# smart_stirrer_proto_mk2.net
KiCad netlist of a schematic drawn in EAGLE
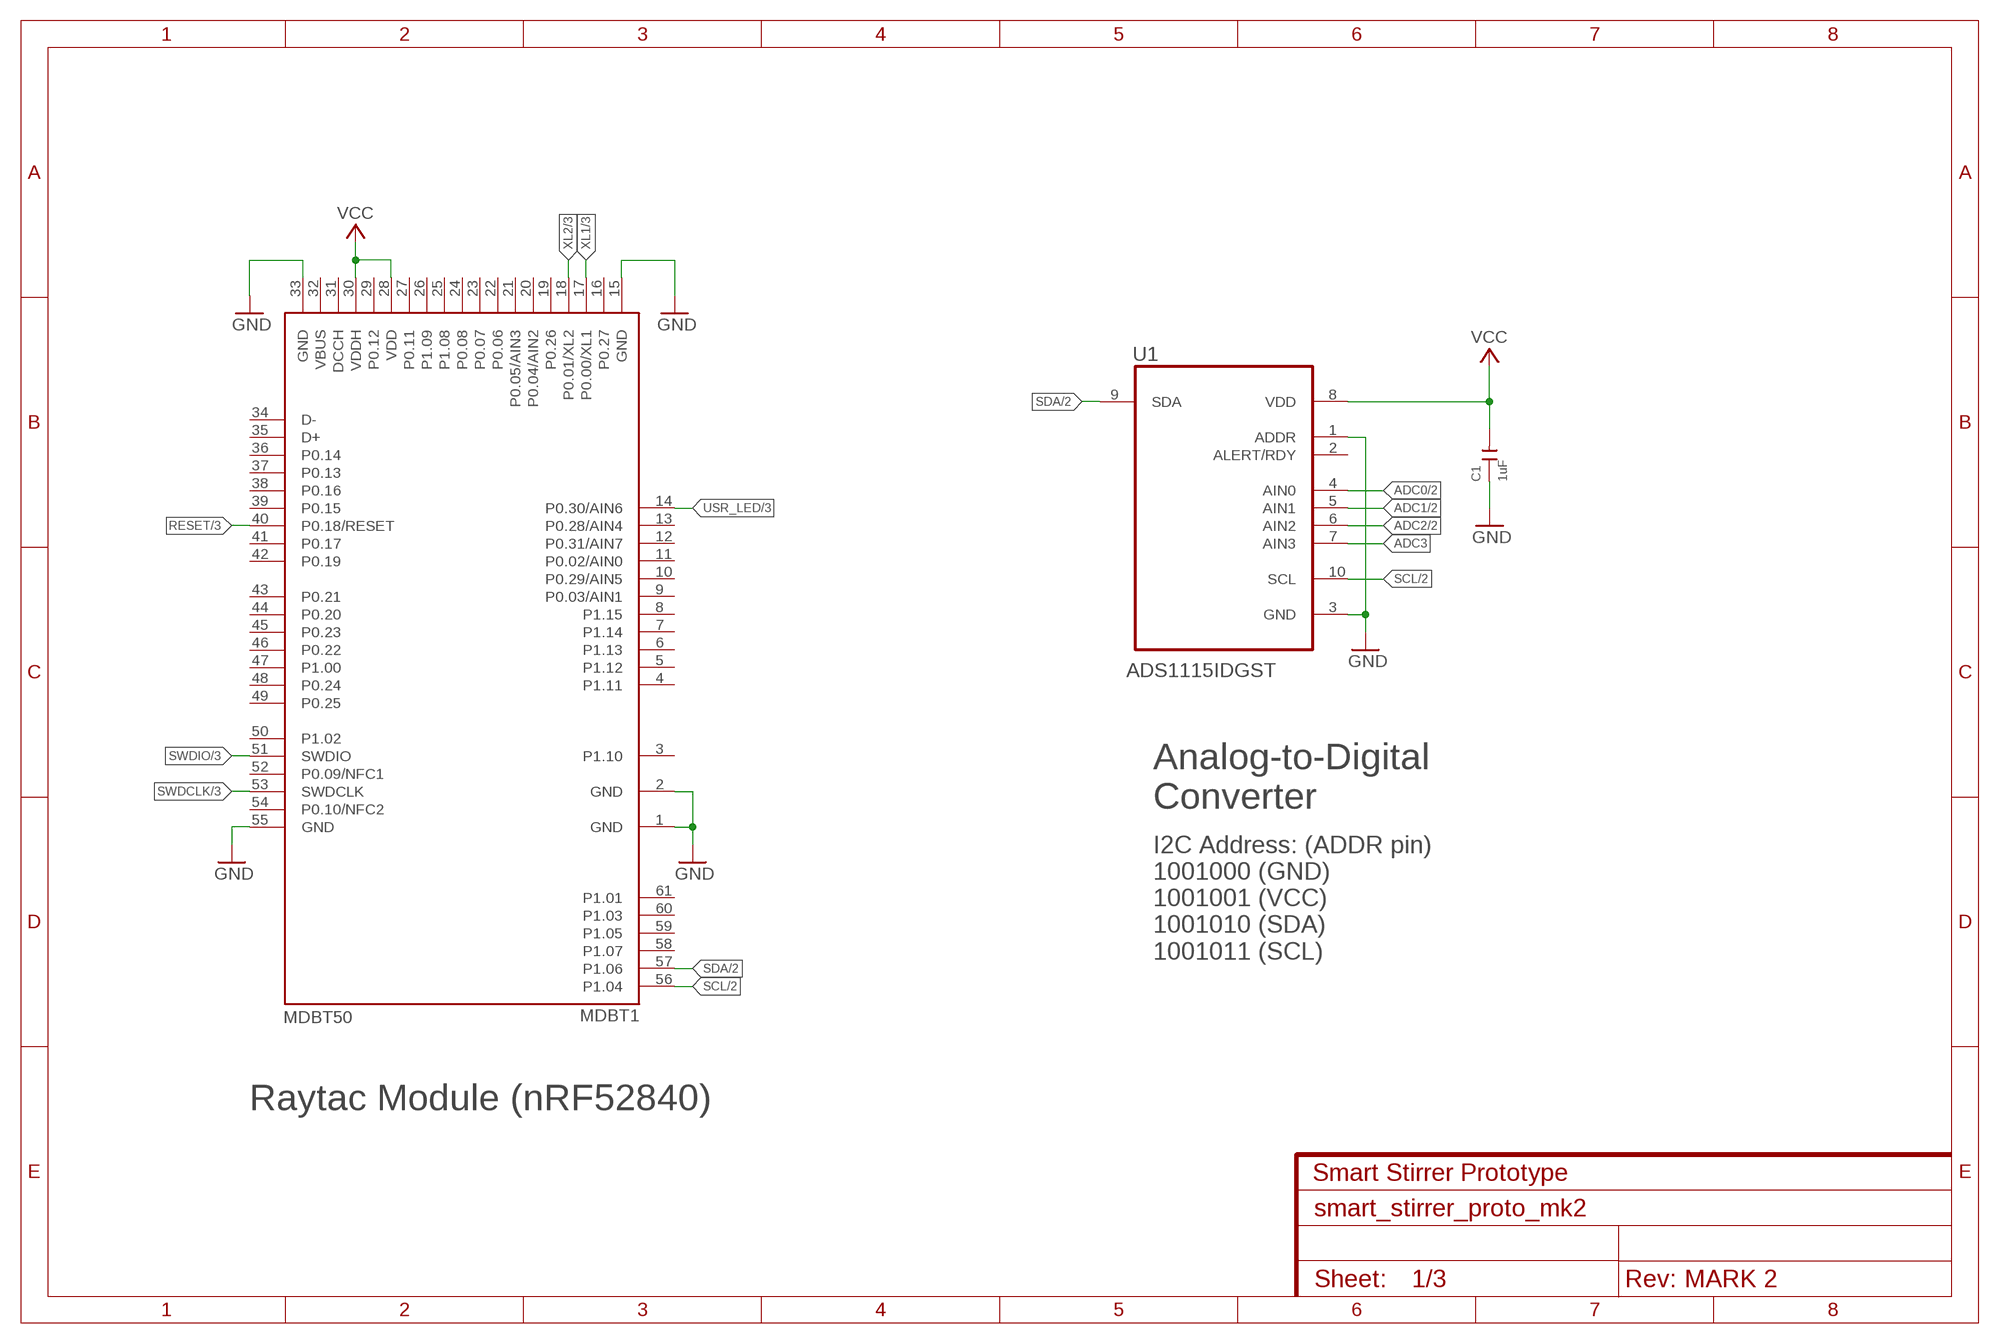
[diagram p0: schematic, sheet 1]
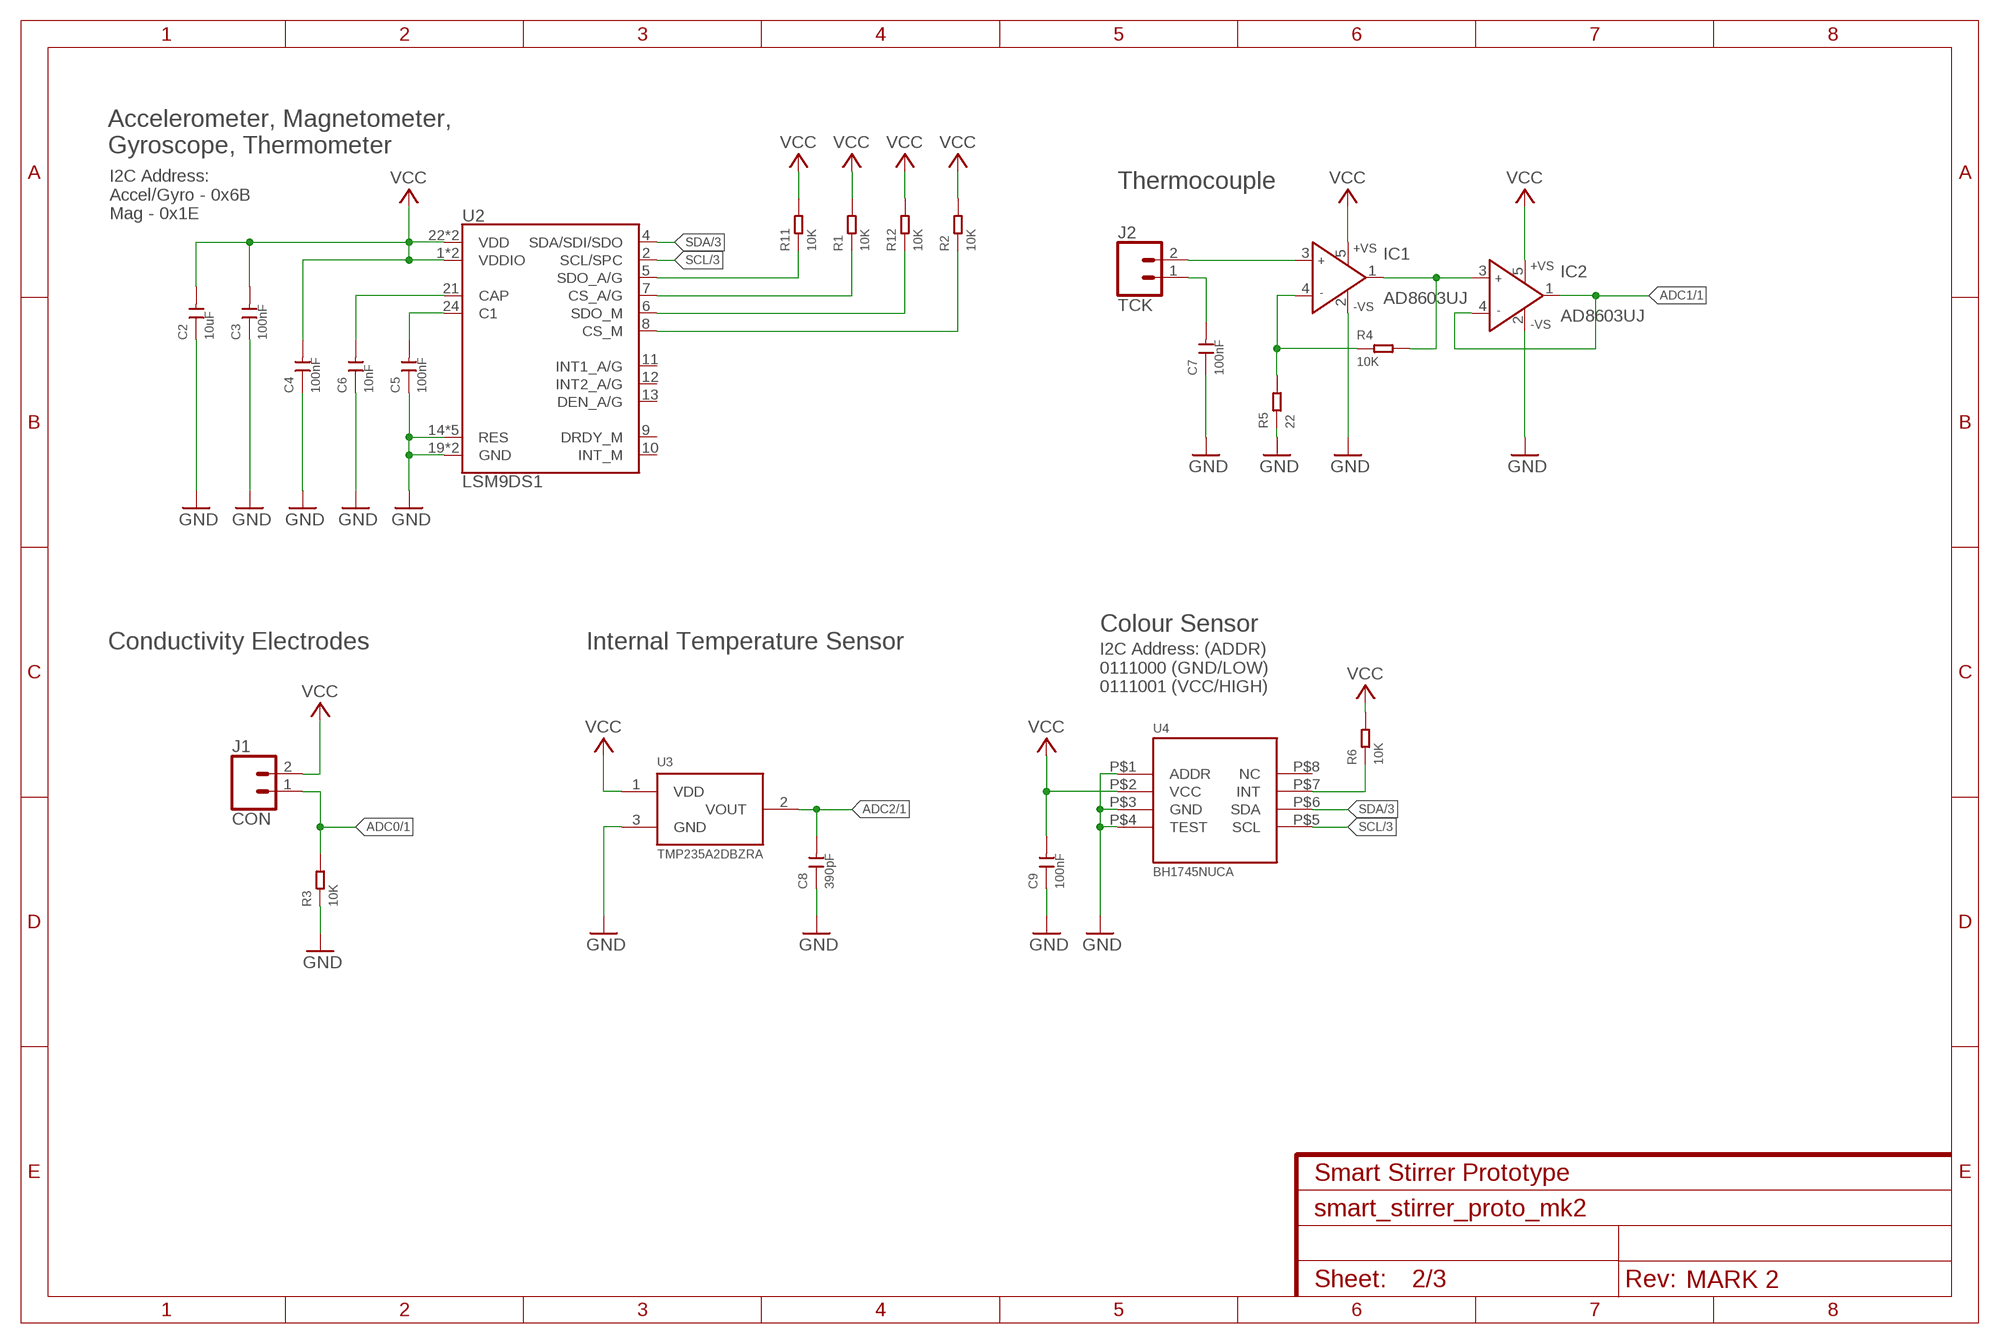
[diagram p1: schematic, sheet 2]
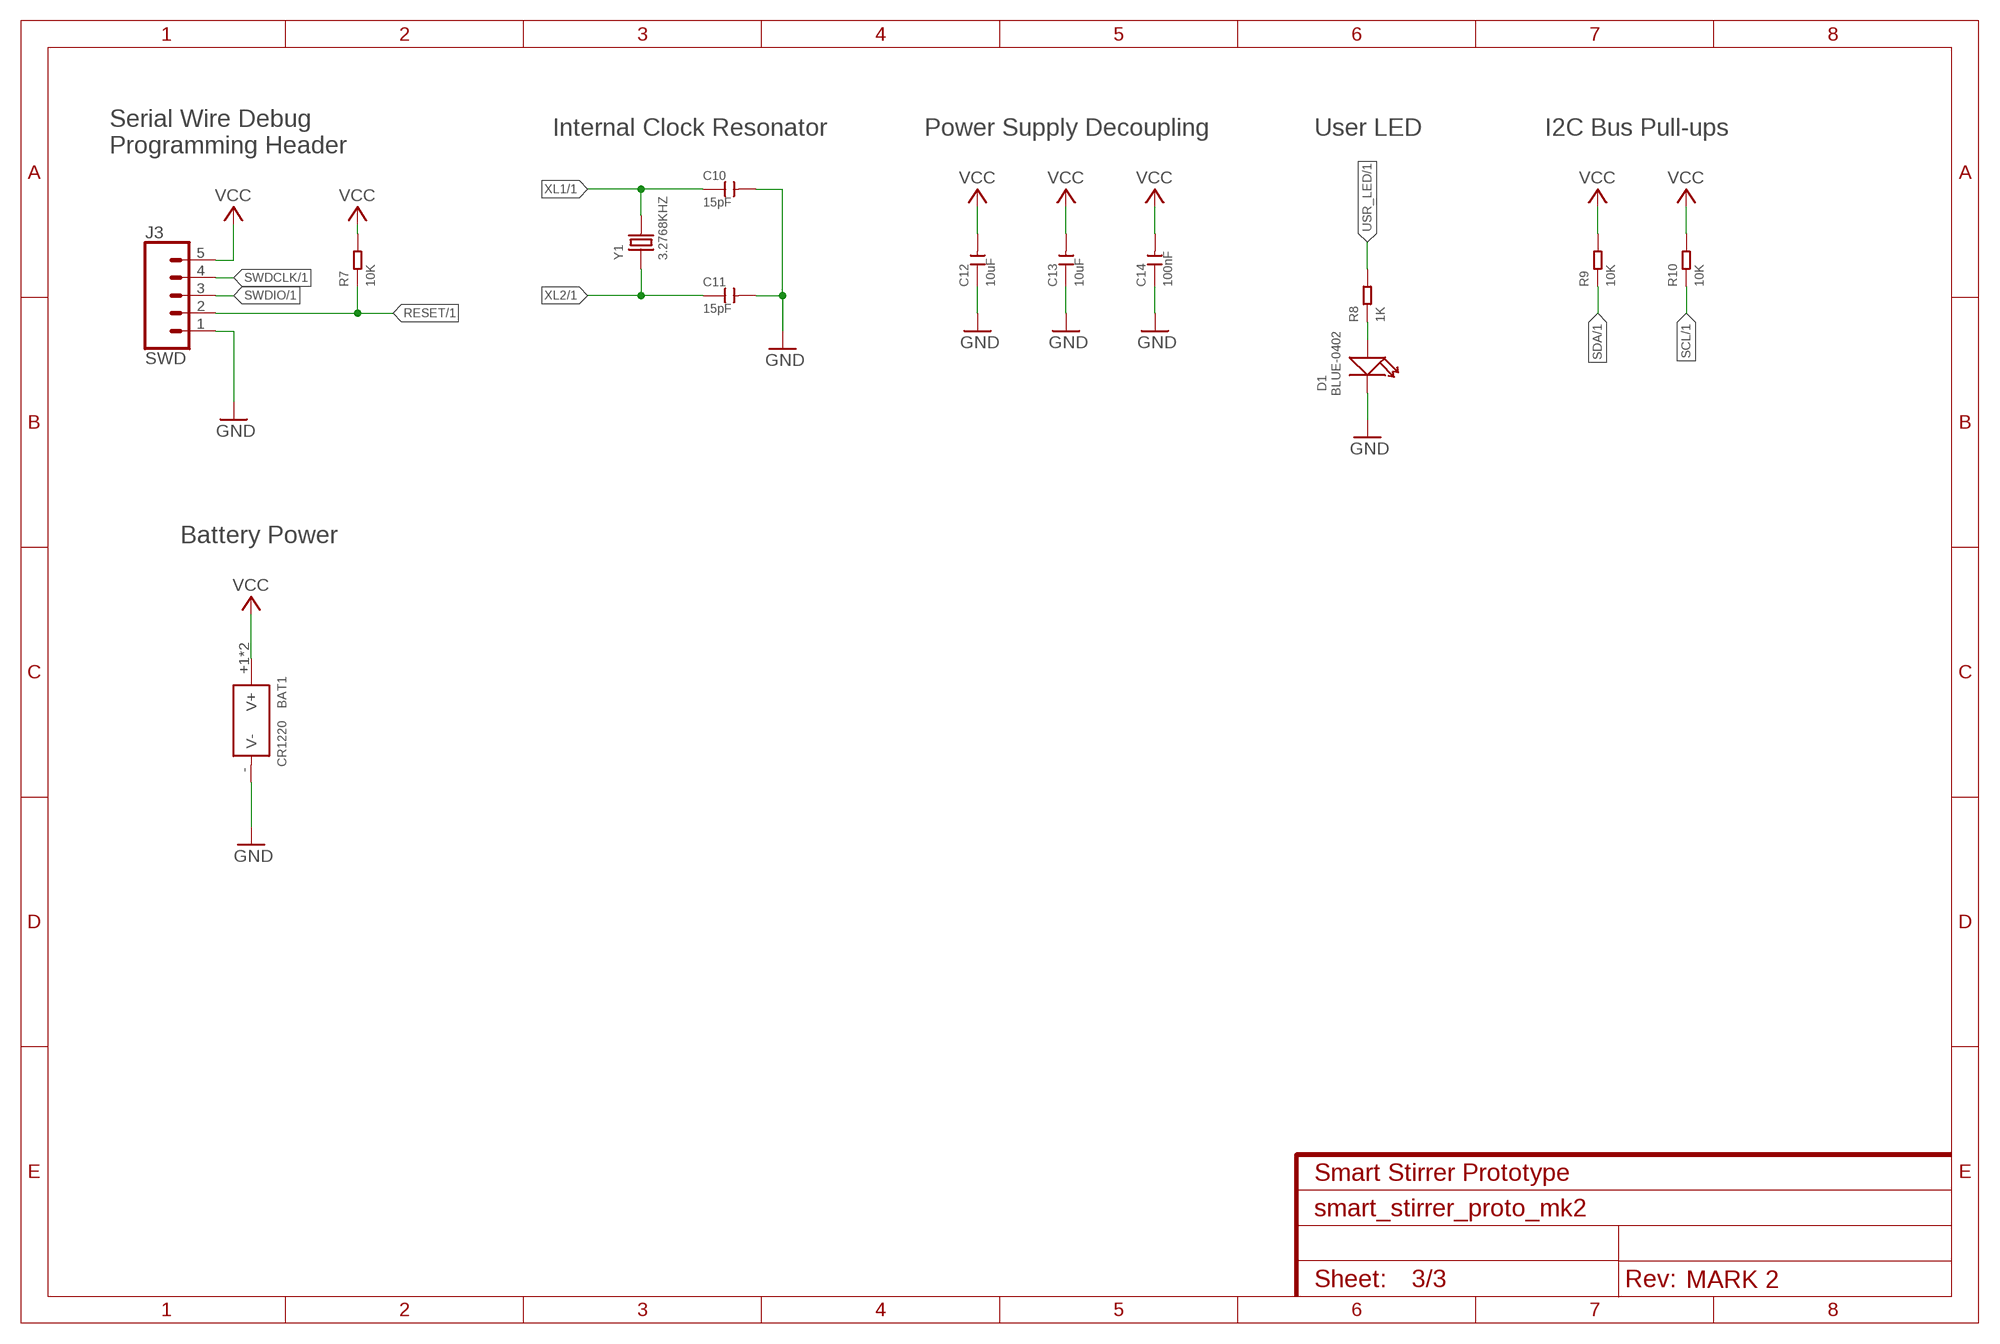
[diagram p2: schematic, sheet 3]

(export (version "E")
  (design (tool "Eeschema 10.0.6"))
  (components
    (comp (ref "C2")
      (value "10uF")
      (footprint "eagle-import:C0402")
      (fields (field (name "MPN") "CC0402MRX5R5BB106"))
      (libsource (lib "eagle-import") (part "CERAMIC-10UF-6.3V-20%-X5R(0402)"))
    )
    (comp (ref "C3")
      (value "100nF")
      (footprint "eagle-import:C0402")
      (fields (field (name "MPN") "CC0402KRX7R8BB104"))
      (libsource (lib "eagle-import") (part "CERAMIC-100NF-25V-10%-X7R(0402)"))
    )
    (comp (ref "C4")
      (value "100nF")
      (footprint "eagle-import:C0402")
      (fields (field (name "MPN") "CC0402KRX7R8BB104"))
      (libsource (lib "eagle-import") (part "CERAMIC-100NF-25V-10%-X7R(0402)"))
    )
    (comp (ref "C5")
      (value "100nF")
      (footprint "eagle-import:C0402")
      (fields (field (name "MPN") "CC0402KRX7R8BB104"))
      (libsource (lib "eagle-import") (part "CERAMIC-100NF-25V-10%-X7R(0402)"))
    )
    (comp (ref "C6")
      (value "10nF")
      (footprint "eagle-import:C0402")
      (fields (field (name "MPN") "CC0402KRX7R9BB103"))
      (libsource (lib "eagle-import") (part "CERAMIC-10NF-50V-10%-X7R(0402)"))
    )
    (comp (ref "C7")
      (value "100nF")
      (footprint "eagle-import:C0402")
      (fields (field (name "MPN") "CC0402KRX7R8BB104"))
      (libsource (lib "eagle-import") (part "OPL_Capacitor_8004261_CERAMIC-100NF-25V-10%-X7R(0402)"))
    )
    (comp (ref "C8")
      (value "390pF")
      (footprint "eagle-import:C0402")
      (fields (field (name "MPN") "CC0402KRX7R9BB391"))
      (libsource (lib "eagle-import") (part "CERAMIC-390PF-50V-10%-X7R(0402)"))
    )
    (comp (ref "C9")
      (value "100nF")
      (footprint "eagle-import:C0402")
      (fields (field (name "MPN") "CC0402KRX7R8BB104"))
      (libsource (lib "eagle-import") (part "OPL_Capacitor_8004261_CERAMIC-100NF-25V-10%-X7R(0402)"))
    )
    (comp (ref "IC1")
      (value "AD8603UJ")
      (footprint "eagle-import:SOT23-5")
      (fields (field (name "MF") "ALTERA CORPORATION") (field (name "MPN") "AD8603AUJZ-REEL7"))
      (libsource (lib "eagle-import") (part "AD8603UJ"))
    )
    (comp (ref "IC2")
      (value "AD8603UJ")
      (footprint "eagle-import:SOT23-5")
      (fields (field (name "MF") "ALTERA CORPORATION") (field (name "MPN") "AD8603AUJZ-REEL7"))
      (libsource (lib "eagle-import") (part "AD8603UJ"))
    )
    (comp (ref "J1")
      (value "CON")
      (footprint "eagle-import:1X02_NO_SILK")
      (libsource (lib "eagle-import") (part "CONN_021X02_NO_SILK"))
    )
    (comp (ref "J2")
      (value "TCK")
      (footprint "eagle-import:1X02_NO_SILK")
      (libsource (lib "eagle-import") (part "CONN_021X02_NO_SILK"))
    )
    (comp (ref "R1")
      (value "10K")
      (footprint "eagle-import:R0402")
      (fields (field (name "MPN") "RC0402JR-0710KL"))
      (libsource (lib "eagle-import") (part "SMD-RES-10K-5%-1/(0402)"))
    )
    (comp (ref "R2")
      (value "10K")
      (footprint "eagle-import:R0402")
      (fields (field (name "MPN") "RC0402JR-0710KL"))
      (libsource (lib "eagle-import") (part "SMD-RES-10K-5%-1/(0402)"))
    )
    (comp (ref "R3")
      (value "10K")
      (footprint "eagle-import:R0402")
      (fields (field (name "MPN") "RC0402JR-0710KL"))
      (libsource (lib "eagle-import") (part "SMD-RES-10K-5%-1/(0402)"))
    )
    (comp (ref "R4")
      (value "10K")
      (footprint "eagle-import:R0402")
      (fields (field (name "MPN") "RC0402JR-0710KL"))
      (libsource (lib "eagle-import") (part "SMD-RES-10K-5%-1/(0402)"))
    )
    (comp (ref "R5")
      (value "22")
      (footprint "eagle-import:R0402")
      (fields (field (name "MPN") "RC0402JR-070RL"))
      (libsource (lib "eagle-import") (part "SMD-RES-22R-5%-1/16W(0402)"))
    )
    (comp (ref "R6")
      (value "10K")
      (footprint "eagle-import:R0402")
      (fields (field (name "MPN") "RC0402JR-0710KL"))
      (libsource (lib "eagle-import") (part "SMD-RES-10K-5%-1/(0402)"))
    )
    (comp (ref "R11")
      (value "10K")
      (footprint "eagle-import:R0402")
      (fields (field (name "MPN") "RC0402JR-0710KL"))
      (libsource (lib "eagle-import") (part "SMD-RES-10K-5%-1/(0402)"))
    )
    (comp (ref "R12")
      (value "10K")
      (footprint "eagle-import:R0402")
      (fields (field (name "MPN") "RC0402JR-0710KL"))
      (libsource (lib "eagle-import") (part "SMD-RES-10K-5%-1/(0402)"))
    )
    (comp (ref "U2")
      (value "LSM9DS1")
      (footprint "eagle-import:LGA24-8X4")
      (libsource (lib "eagle-import") (part "LSM9DS1"))
    )
    (comp (ref "U3")
      (value "TMP235A2DBZRA")
      (footprint "eagle-import:SOT-23-3")
      (libsource (lib "eagle-import") (part "TMP235A2DBZRA"))
    )
    (comp (ref "U4")
      (value "BH1745NUCA")
      (footprint "eagle-import:BH1745NUC-E2")
      (libsource (lib "eagle-import") (part "BH1745NUCA"))
    )
    (comp (ref "C1")
      (value "1uF")
      (footprint "eagle-import:C0402")
      (fields (field (name "MPN") "CC0402KRX5R6BB105"))
      (libsource (lib "eagle-import") (part "CERAMIC-1UF-10V-10%-X5R(0402)"))
    )
    (comp (ref "MDBT1")
      (value "MDBT50")
      (footprint "eagle-import:MDBT50")
      (libsource (lib "eagle-import") (part "MDBT50"))
    )
    (comp (ref "U1")
      (value "ADS1115IDGST")
      (footprint "eagle-import:SOP50P490X110-10N")
      (fields (field (name "MF") "Texas Instruments"))
      (libsource (lib "eagle-import") (part "ADS1115IDGST"))
    )
    (comp (ref "BAT1")
      (value "CR1220")
      (footprint "eagle-import:BAT2P-13.5-CR1220")
      (libsource (lib "eagle-import") (part "DIP-BATTERY-CELL-HOLDER(1220)"))
    )
    (comp (ref "C10")
      (value "15pF")
      (footprint "eagle-import:C0402")
      (fields (field (name "MPN") "GRM1555C1H150JA01D"))
      (libsource (lib "eagle-import") (part "CERAMIC-15PF-50V-5%-NPO(0402)"))
    )
    (comp (ref "C11")
      (value "15pF")
      (footprint "eagle-import:C0402")
      (fields (field (name "MPN") "GRM1555C1H150JA01D"))
      (libsource (lib "eagle-import") (part "CERAMIC-15PF-50V-5%-NPO(0402)"))
    )
    (comp (ref "C12")
      (value "10uF")
      (footprint "eagle-import:C0402")
      (fields (field (name "MPN") "CC0402MRX5R5BB106"))
      (libsource (lib "eagle-import") (part "OPL_Capacitor_8004261_CERAMIC-10UF-6.3V-20%-X5R(0402)"))
    )
    (comp (ref "C13")
      (value "10uF")
      (footprint "eagle-import:C0402")
      (fields (field (name "MPN") "CC0402MRX5R5BB106"))
      (libsource (lib "eagle-import") (part "OPL_Capacitor_8004261_CERAMIC-10UF-6.3V-20%-X5R(0402)"))
    )
    (comp (ref "C14")
      (value "100nF")
      (footprint "eagle-import:C0402")
      (fields (field (name "MPN") "CC0402KRX7R8BB104"))
      (libsource (lib "eagle-import") (part "OPL_Capacitor_8004261_CERAMIC-100NF-25V-10%-X7R(0402)"))
    )
    (comp (ref "D1")
      (value "BLUE-0402")
      (footprint "eagle-import:LED-0402")
      (fields (field (name "MPN") "BL-HB337A-AV-TRB"))
      (libsource (lib "eagle-import") (part "SMD-LED-CLEAR-BLUE(0402)"))
    )
    (comp (ref "J3")
      (value "SWD")
      (footprint "eagle-import:1X05_NO_SILK")
      (libsource (lib "eagle-import") (part "CONN_05NO_SILK"))
    )
    (comp (ref "R7")
      (value "10K")
      (footprint "eagle-import:R0402")
      (fields (field (name "MPN") "RC0402JR-0710KL"))
      (libsource (lib "eagle-import") (part "SMD-RES-10K-5%-1/(0402)"))
    )
    (comp (ref "R8")
      (value "1K")
      (footprint "eagle-import:R0402")
      (fields (field (name "MPN") "RC0402JR-071KL"))
      (libsource (lib "eagle-import") (part "SMD-RES-1K-5%-1/16W(0402)"))
    )
    (comp (ref "R9")
      (value "10K")
      (footprint "eagle-import:R0402")
      (fields (field (name "MPN") "RC0402JR-0710KL"))
      (libsource (lib "eagle-import") (part "SMD-RES-10K-5%-1/(0402)"))
    )
    (comp (ref "R10")
      (value "10K")
      (footprint "eagle-import:R0402")
      (fields (field (name "MPN") "RC0402JR-0710KL"))
      (libsource (lib "eagle-import") (part "SMD-RES-10K-5%-1/(0402)"))
    )
    (comp (ref "Y1")
      (value "3.2768KHZ")
      (footprint "eagle-import:X2-SMD-L2.0X1.2X0.55MM")
      (fields (field (name "MPN") "FC-12M"))
      (libsource (lib "eagle-import") (part "SMD-CRYSTAL-32.768KHZ-12.5PF-20PPM-90K(2P-L2.0X1.2MM)"))
    )
  )
  (nets
    (net (code "1") (name "ADC0") (class "Default")
      (node (ref "J1") (pin "1") (pinfunction "1_1") (pintype "passive"))
      (node (ref "R3") (pin "2") (pinfunction "2_2") (pintype "passive"))
      (node (ref "U1") (pin "4") (pinfunction "AIN0_4") (pintype "input"))
    )
    (net (code "2") (name "ADC1") (class "Default")
      (node (ref "IC2") (pin "1") (pinfunction "OUT_1") (pintype "output"))
      (node (ref "IC2") (pin "4") (pinfunction "IN-_4") (pintype "input"))
      (node (ref "U1") (pin "5") (pinfunction "AIN1_5") (pintype "input"))
    )
    (net (code "3") (name "ADC2") (class "Default")
      (node (ref "C8") (pin "2") (pinfunction "2_2") (pintype "passive"))
      (node (ref "U1") (pin "6") (pinfunction "AIN2_6") (pintype "input"))
      (node (ref "U3") (pin "2") (pinfunction "VOUT_2") (pintype "bidirectional"))
    )
    (net (code "4") (name "ADC3") (class "Default")
      (node (ref "U1") (pin "7") (pinfunction "AIN3_7") (pintype "input"))
    )
    (net (code "5") (name "GND") (class "Default")
      (node (ref "BAT1") (pin "-") (pinfunction "V-_-") (pintype "bidirectional"))
      (node (ref "C1") (pin "1") (pinfunction "1_1") (pintype "passive"))
      (node (ref "C10") (pin "2") (pinfunction "2_2") (pintype "passive"))
      (node (ref "C11") (pin "2") (pinfunction "2_2") (pintype "passive"))
      (node (ref "C12") (pin "1") (pinfunction "1_1") (pintype "passive"))
      (node (ref "C13") (pin "1") (pinfunction "1_1") (pintype "passive"))
      (node (ref "C14") (pin "1") (pinfunction "1_1") (pintype "passive"))
      (node (ref "C2") (pin "1") (pinfunction "1_1") (pintype "passive"))
      (node (ref "C3") (pin "1") (pinfunction "1_1") (pintype "passive"))
      (node (ref "C4") (pin "1") (pinfunction "1_1") (pintype "passive"))
      (node (ref "C5") (pin "1") (pinfunction "1_1") (pintype "passive"))
      (node (ref "C6") (pin "1") (pinfunction "1_1") (pintype "passive"))
      (node (ref "C7") (pin "1") (pinfunction "1_1") (pintype "passive"))
      (node (ref "C8") (pin "1") (pinfunction "1_1") (pintype "passive"))
      (node (ref "C9") (pin "1") (pinfunction "1_1") (pintype "passive"))
      (node (ref "D1") (pin "-") (pinfunction "-_-") (pintype "passive"))
      (node (ref "IC1") (pin "2") (pinfunction "-VS_2") (pintype "input"))
      (node (ref "IC2") (pin "2") (pinfunction "-VS_2") (pintype "input"))
      (node (ref "J3") (pin "1") (pinfunction "1_1") (pintype "passive"))
      (node (ref "MDBT1") (pin "1") (pinfunction "GND_1") (pintype "bidirectional"))
      (node (ref "MDBT1") (pin "15") (pinfunction "GND_15") (pintype "bidirectional"))
      (node (ref "MDBT1") (pin "2") (pinfunction "GND_2") (pintype "bidirectional"))
      (node (ref "MDBT1") (pin "33") (pinfunction "GND_33") (pintype "bidirectional"))
      (node (ref "MDBT1") (pin "55") (pinfunction "GND_55") (pintype "bidirectional"))
      (node (ref "R3") (pin "1") (pinfunction "1_1") (pintype "passive"))
      (node (ref "R5") (pin "1") (pinfunction "1_1") (pintype "passive"))
      (node (ref "U1") (pin "1") (pinfunction "ADDR_1") (pintype "input"))
      (node (ref "U1") (pin "3") (pinfunction "GND_3") (pintype "passive"))
      (node (ref "U2") (pin "14") (pinfunction "RES_14") (pintype "bidirectional"))
      (node (ref "U2") (pin "15") (pinfunction "RES_15") (pintype "bidirectional"))
      (node (ref "U2") (pin "16") (pinfunction "RES_16") (pintype "bidirectional"))
      (node (ref "U2") (pin "17") (pinfunction "RES_17") (pintype "bidirectional"))
      (node (ref "U2") (pin "18") (pinfunction "RES_18") (pintype "bidirectional"))
      (node (ref "U2") (pin "19") (pinfunction "GND_19") (pintype "bidirectional"))
      (node (ref "U2") (pin "20") (pinfunction "GND_20") (pintype "bidirectional"))
      (node (ref "U3") (pin "3") (pinfunction "GND_3") (pintype "bidirectional"))
      (node (ref "U4") (pin "P$1") (pinfunction "ADDR_P$1") (pintype "bidirectional"))
      (node (ref "U4") (pin "P$3") (pinfunction "GND_P$3") (pintype "bidirectional"))
      (node (ref "U4") (pin "P$4") (pinfunction "TEST_P$4") (pintype "bidirectional"))
    )
    (net (code "6") (name "Net-(C7-Pad2)") (class "Default")
      (node (ref "C7") (pin "2") (pinfunction "2_2") (pintype "passive"))
      (node (ref "J2") (pin "1") (pinfunction "1_1") (pintype "passive"))
    )
    (net (code "7") (name "Net-(D1-Pad+)") (class "Default")
      (node (ref "D1") (pin "+") (pinfunction "+_+") (pintype "passive"))
      (node (ref "R8") (pin "1") (pinfunction "1_1") (pintype "passive"))
    )
    (net (code "8") (name "Net-(IC1-IN+)") (class "Default")
      (node (ref "IC1") (pin "3") (pinfunction "IN+_3") (pintype "input"))
      (node (ref "J2") (pin "2") (pinfunction "2_2") (pintype "passive"))
    )
    (net (code "9") (name "Net-(IC1-IN-)") (class "Default")
      (node (ref "IC1") (pin "4") (pinfunction "IN-_4") (pintype "input"))
      (node (ref "R4") (pin "1") (pinfunction "1_1") (pintype "passive"))
      (node (ref "R5") (pin "2") (pinfunction "2_2") (pintype "passive"))
    )
    (net (code "10") (name "Net-(IC1-OUT)") (class "Default")
      (node (ref "IC1") (pin "1") (pinfunction "OUT_1") (pintype "output"))
      (node (ref "IC2") (pin "3") (pinfunction "IN+_3") (pintype "input"))
      (node (ref "R4") (pin "2") (pinfunction "2_2") (pintype "passive"))
    )
    (net (code "11") (name "Net-(U2-C1)") (class "Default")
      (node (ref "C5") (pin "2") (pinfunction "2_2") (pintype "passive"))
      (node (ref "U2") (pin "24") (pinfunction "C1_24") (pintype "bidirectional"))
    )
    (net (code "12") (name "Net-(U2-CAP)") (class "Default")
      (node (ref "C6") (pin "2") (pinfunction "2_2") (pintype "passive"))
      (node (ref "U2") (pin "21") (pinfunction "CAP_21") (pintype "bidirectional"))
    )
    (net (code "13") (name "Net-(U2-CS_A{slash}G)") (class "Default")
      (node (ref "R1") (pin "1") (pinfunction "1_1") (pintype "passive"))
      (node (ref "U2") (pin "7") (pinfunction "CS_A/G_7") (pintype "bidirectional"))
    )
    (net (code "14") (name "Net-(U2-CS_M)") (class "Default")
      (node (ref "R2") (pin "1") (pinfunction "1_1") (pintype "passive"))
      (node (ref "U2") (pin "8") (pinfunction "CS_M_8") (pintype "bidirectional"))
    )
    (net (code "15") (name "Net-(U2-SDO_A{slash}G)") (class "Default")
      (node (ref "R11") (pin "1") (pinfunction "1_1") (pintype "passive"))
      (node (ref "U2") (pin "5") (pinfunction "SDO_A/G_5") (pintype "bidirectional"))
    )
    (net (code "16") (name "Net-(U2-SDO_M)") (class "Default")
      (node (ref "R12") (pin "1") (pinfunction "1_1") (pintype "passive"))
      (node (ref "U2") (pin "6") (pinfunction "SDO_M_6") (pintype "bidirectional"))
    )
    (net (code "17") (name "Net-(U4-INT)") (class "Default")
      (node (ref "R6") (pin "1") (pinfunction "1_1") (pintype "passive"))
      (node (ref "U4") (pin "P$7") (pinfunction "INT_P$7") (pintype "bidirectional"))
    )
    (net (code "18") (name "RESET") (class "Default")
      (node (ref "J3") (pin "2") (pinfunction "2_2") (pintype "passive"))
      (node (ref "MDBT1") (pin "40") (pinfunction "P0.18/RESET_40") (pintype "bidirectional"))
      (node (ref "R7") (pin "1") (pinfunction "1_1") (pintype "passive"))
    )
    (net (code "19") (name "SCL") (class "Default")
      (node (ref "MDBT1") (pin "56") (pinfunction "P1.04_56") (pintype "bidirectional"))
      (node (ref "R10") (pin "1") (pinfunction "1_1") (pintype "passive"))
      (node (ref "U1") (pin "10") (pinfunction "SCL_10") (pintype "input"))
      (node (ref "U2") (pin "2") (pinfunction "SCL/SPC_2") (pintype "bidirectional"))
      (node (ref "U4") (pin "P$5") (pinfunction "SCL_P$5") (pintype "bidirectional"))
    )
    (net (code "20") (name "SDA") (class "Default")
      (node (ref "MDBT1") (pin "57") (pinfunction "P1.06_57") (pintype "bidirectional"))
      (node (ref "R9") (pin "1") (pinfunction "1_1") (pintype "passive"))
      (node (ref "U1") (pin "9") (pinfunction "SDA_9") (pintype "bidirectional"))
      (node (ref "U2") (pin "4") (pinfunction "SDA/SDI/SDO_4") (pintype "bidirectional"))
      (node (ref "U4") (pin "P$6") (pinfunction "SDA_P$6") (pintype "bidirectional"))
    )
    (net (code "21") (name "SWDCLK") (class "Default")
      (node (ref "J3") (pin "4") (pinfunction "4_4") (pintype "passive"))
      (node (ref "MDBT1") (pin "53") (pinfunction "SWDCLK_53") (pintype "bidirectional"))
    )
    (net (code "22") (name "SWDIO") (class "Default")
      (node (ref "J3") (pin "3") (pinfunction "3_3") (pintype "passive"))
      (node (ref "MDBT1") (pin "51") (pinfunction "SWDIO_51") (pintype "bidirectional"))
    )
    (net (code "23") (name "USR_LED") (class "Default")
      (node (ref "MDBT1") (pin "14") (pinfunction "P0.30/AIN6_14") (pintype "bidirectional"))
      (node (ref "R8") (pin "2") (pinfunction "2_2") (pintype "passive"))
    )
    (net (code "24") (name "VCC") (class "Default")
      (node (ref "BAT1") (pin "+1") (pinfunction "V+_+1") (pintype "bidirectional"))
      (node (ref "BAT1") (pin "+2") (pinfunction "V+_+2") (pintype "bidirectional"))
      (node (ref "C1") (pin "2") (pinfunction "2_2") (pintype "passive"))
      (node (ref "C12") (pin "2") (pinfunction "2_2") (pintype "passive"))
      (node (ref "C13") (pin "2") (pinfunction "2_2") (pintype "passive"))
      (node (ref "C14") (pin "2") (pinfunction "2_2") (pintype "passive"))
      (node (ref "C2") (pin "2") (pinfunction "2_2") (pintype "passive"))
      (node (ref "C3") (pin "2") (pinfunction "2_2") (pintype "passive"))
      (node (ref "C4") (pin "2") (pinfunction "2_2") (pintype "passive"))
      (node (ref "C9") (pin "2") (pinfunction "2_2") (pintype "passive"))
      (node (ref "IC1") (pin "5") (pinfunction "+VS_5") (pintype "input"))
      (node (ref "IC2") (pin "5") (pinfunction "+VS_5") (pintype "input"))
      (node (ref "J1") (pin "2") (pinfunction "2_2") (pintype "passive"))
      (node (ref "J3") (pin "5") (pinfunction "5_5") (pintype "passive"))
      (node (ref "MDBT1") (pin "28") (pinfunction "VDD_28") (pintype "bidirectional"))
      (node (ref "MDBT1") (pin "30") (pinfunction "VDDH_30") (pintype "bidirectional"))
      (node (ref "R1") (pin "2") (pinfunction "2_2") (pintype "passive"))
      (node (ref "R10") (pin "2") (pinfunction "2_2") (pintype "passive"))
      (node (ref "R11") (pin "2") (pinfunction "2_2") (pintype "passive"))
      (node (ref "R12") (pin "2") (pinfunction "2_2") (pintype "passive"))
      (node (ref "R2") (pin "2") (pinfunction "2_2") (pintype "passive"))
      (node (ref "R6") (pin "2") (pinfunction "2_2") (pintype "passive"))
      (node (ref "R7") (pin "2") (pinfunction "2_2") (pintype "passive"))
      (node (ref "R9") (pin "2") (pinfunction "2_2") (pintype "passive"))
      (node (ref "U1") (pin "8") (pinfunction "VDD_8") (pintype "power_in"))
      (node (ref "U2") (pin "1") (pinfunction "VDDIO_1") (pintype "bidirectional"))
      (node (ref "U2") (pin "22") (pinfunction "VDD_22") (pintype "bidirectional"))
      (node (ref "U2") (pin "23") (pinfunction "VDD_23") (pintype "bidirectional"))
      (node (ref "U2") (pin "3") (pinfunction "VDDIO_3") (pintype "bidirectional"))
      (node (ref "U3") (pin "1") (pinfunction "VDD_1") (pintype "bidirectional"))
      (node (ref "U4") (pin "P$2") (pinfunction "VCC_P$2") (pintype "bidirectional"))
    )
    (net (code "25") (name "XL1") (class "Default")
      (node (ref "C10") (pin "1") (pinfunction "1_1") (pintype "passive"))
      (node (ref "MDBT1") (pin "17") (pinfunction "P0.00/XL1_17") (pintype "bidirectional"))
      (node (ref "Y1") (pin "2") (pinfunction "2_2") (pintype "passive"))
    )
    (net (code "26") (name "XL2") (class "Default")
      (node (ref "C11") (pin "1") (pinfunction "1_1") (pintype "passive"))
      (node (ref "MDBT1") (pin "18") (pinfunction "P0.01/XL2_18") (pintype "bidirectional"))
      (node (ref "Y1") (pin "1") (pinfunction "1_1") (pintype "passive"))
    )
    (net (code "27") (name "unconnected-(MDBT1-D+-Pad35)") (class "Default")
      (node (ref "MDBT1") (pin "35") (pinfunction "D+_35") (pintype "bidirectional"))
    )
    (net (code "28") (name "unconnected-(MDBT1-D--Pad34)") (class "Default")
      (node (ref "MDBT1") (pin "34") (pinfunction "D-_34") (pintype "bidirectional"))
    )
    (net (code "29") (name "unconnected-(MDBT1-DCCH-Pad31)") (class "Default")
      (node (ref "MDBT1") (pin "31") (pinfunction "DCCH_31") (pintype "bidirectional"))
    )
    (net (code "30") (name "unconnected-(MDBT1-P0.02{slash}AIN0-Pad11)") (class "Default")
      (node (ref "MDBT1") (pin "11") (pinfunction "P0.02/AIN0_11") (pintype "bidirectional"))
    )
    (net (code "31") (name "unconnected-(MDBT1-P0.03{slash}AIN1-Pad9)") (class "Default")
      (node (ref "MDBT1") (pin "9") (pinfunction "P0.03/AIN1_9") (pintype "bidirectional"))
    )
    (net (code "32") (name "unconnected-(MDBT1-P0.04{slash}AIN2-Pad20)") (class "Default")
      (node (ref "MDBT1") (pin "20") (pinfunction "P0.04/AIN2_20") (pintype "bidirectional"))
    )
    (net (code "33") (name "unconnected-(MDBT1-P0.05{slash}AIN3-Pad21)") (class "Default")
      (node (ref "MDBT1") (pin "21") (pinfunction "P0.05/AIN3_21") (pintype "bidirectional"))
    )
    (net (code "34") (name "unconnected-(MDBT1-P0.06-Pad22)") (class "Default")
      (node (ref "MDBT1") (pin "22") (pinfunction "P0.06_22") (pintype "bidirectional"))
    )
    (net (code "35") (name "unconnected-(MDBT1-P0.07-Pad23)") (class "Default")
      (node (ref "MDBT1") (pin "23") (pinfunction "P0.07_23") (pintype "bidirectional"))
    )
    (net (code "36") (name "unconnected-(MDBT1-P0.08-Pad24)") (class "Default")
      (node (ref "MDBT1") (pin "24") (pinfunction "P0.08_24") (pintype "bidirectional"))
    )
    (net (code "37") (name "unconnected-(MDBT1-P0.09{slash}NFC1-Pad52)") (class "Default")
      (node (ref "MDBT1") (pin "52") (pinfunction "P0.09/NFC1_52") (pintype "bidirectional"))
    )
    (net (code "38") (name "unconnected-(MDBT1-P0.10{slash}NFC2-Pad54)") (class "Default")
      (node (ref "MDBT1") (pin "54") (pinfunction "P0.10/NFC2_54") (pintype "bidirectional"))
    )
    (net (code "39") (name "unconnected-(MDBT1-P0.11-Pad27)") (class "Default")
      (node (ref "MDBT1") (pin "27") (pinfunction "P0.11_27") (pintype "bidirectional"))
    )
    (net (code "40") (name "unconnected-(MDBT1-P0.12-Pad29)") (class "Default")
      (node (ref "MDBT1") (pin "29") (pinfunction "P0.12_29") (pintype "bidirectional"))
    )
    (net (code "41") (name "unconnected-(MDBT1-P0.13-Pad37)") (class "Default")
      (node (ref "MDBT1") (pin "37") (pinfunction "P0.13_37") (pintype "bidirectional"))
    )
    (net (code "42") (name "unconnected-(MDBT1-P0.14-Pad36)") (class "Default")
      (node (ref "MDBT1") (pin "36") (pinfunction "P0.14_36") (pintype "bidirectional"))
    )
    (net (code "43") (name "unconnected-(MDBT1-P0.15-Pad39)") (class "Default")
      (node (ref "MDBT1") (pin "39") (pinfunction "P0.15_39") (pintype "bidirectional"))
    )
    (net (code "44") (name "unconnected-(MDBT1-P0.16-Pad38)") (class "Default")
      (node (ref "MDBT1") (pin "38") (pinfunction "P0.16_38") (pintype "bidirectional"))
    )
    (net (code "45") (name "unconnected-(MDBT1-P0.17-Pad41)") (class "Default")
      (node (ref "MDBT1") (pin "41") (pinfunction "P0.17_41") (pintype "bidirectional"))
    )
    (net (code "46") (name "unconnected-(MDBT1-P0.19-Pad42)") (class "Default")
      (node (ref "MDBT1") (pin "42") (pinfunction "P0.19_42") (pintype "bidirectional"))
    )
    (net (code "47") (name "unconnected-(MDBT1-P0.20-Pad44)") (class "Default")
      (node (ref "MDBT1") (pin "44") (pinfunction "P0.20_44") (pintype "bidirectional"))
    )
    (net (code "48") (name "unconnected-(MDBT1-P0.21-Pad43)") (class "Default")
      (node (ref "MDBT1") (pin "43") (pinfunction "P0.21_43") (pintype "bidirectional"))
    )
    (net (code "49") (name "unconnected-(MDBT1-P0.22-Pad46)") (class "Default")
      (node (ref "MDBT1") (pin "46") (pinfunction "P0.22_46") (pintype "bidirectional"))
    )
    (net (code "50") (name "unconnected-(MDBT1-P0.23-Pad45)") (class "Default")
      (node (ref "MDBT1") (pin "45") (pinfunction "P0.23_45") (pintype "bidirectional"))
    )
    (net (code "51") (name "unconnected-(MDBT1-P0.24-Pad48)") (class "Default")
      (node (ref "MDBT1") (pin "48") (pinfunction "P0.24_48") (pintype "bidirectional"))
    )
    (net (code "52") (name "unconnected-(MDBT1-P0.25-Pad49)") (class "Default")
      (node (ref "MDBT1") (pin "49") (pinfunction "P0.25_49") (pintype "bidirectional"))
    )
    (net (code "53") (name "unconnected-(MDBT1-P0.26-Pad19)") (class "Default")
      (node (ref "MDBT1") (pin "19") (pinfunction "P0.26_19") (pintype "bidirectional"))
    )
    (net (code "54") (name "unconnected-(MDBT1-P0.27-Pad16)") (class "Default")
      (node (ref "MDBT1") (pin "16") (pinfunction "P0.27_16") (pintype "bidirectional"))
    )
    (net (code "55") (name "unconnected-(MDBT1-P0.28{slash}AIN4-Pad13)") (class "Default")
      (node (ref "MDBT1") (pin "13") (pinfunction "P0.28/AIN4_13") (pintype "bidirectional"))
    )
    (net (code "56") (name "unconnected-(MDBT1-P0.29{slash}AIN5-Pad10)") (class "Default")
      (node (ref "MDBT1") (pin "10") (pinfunction "P0.29/AIN5_10") (pintype "bidirectional"))
    )
    (net (code "57") (name "unconnected-(MDBT1-P0.31{slash}AIN7-Pad12)") (class "Default")
      (node (ref "MDBT1") (pin "12") (pinfunction "P0.31/AIN7_12") (pintype "bidirectional"))
    )
    (net (code "58") (name "unconnected-(MDBT1-P1.00-Pad47)") (class "Default")
      (node (ref "MDBT1") (pin "47") (pinfunction "P1.00_47") (pintype "bidirectional"))
    )
    (net (code "59") (name "unconnected-(MDBT1-P1.01-Pad61)") (class "Default")
      (node (ref "MDBT1") (pin "61") (pinfunction "P1.01_61") (pintype "bidirectional"))
    )
    (net (code "60") (name "unconnected-(MDBT1-P1.02-Pad50)") (class "Default")
      (node (ref "MDBT1") (pin "50") (pinfunction "P1.02_50") (pintype "bidirectional"))
    )
    (net (code "61") (name "unconnected-(MDBT1-P1.03-Pad60)") (class "Default")
      (node (ref "MDBT1") (pin "60") (pinfunction "P1.03_60") (pintype "bidirectional"))
    )
    (net (code "62") (name "unconnected-(MDBT1-P1.05-Pad59)") (class "Default")
      (node (ref "MDBT1") (pin "59") (pinfunction "P1.05_59") (pintype "bidirectional"))
    )
    (net (code "63") (name "unconnected-(MDBT1-P1.07-Pad58)") (class "Default")
      (node (ref "MDBT1") (pin "58") (pinfunction "P1.07_58") (pintype "bidirectional"))
    )
    (net (code "64") (name "unconnected-(MDBT1-P1.08-Pad25)") (class "Default")
      (node (ref "MDBT1") (pin "25") (pinfunction "P1.08_25") (pintype "bidirectional"))
    )
    (net (code "65") (name "unconnected-(MDBT1-P1.09-Pad26)") (class "Default")
      (node (ref "MDBT1") (pin "26") (pinfunction "P1.09_26") (pintype "bidirectional"))
    )
    (net (code "66") (name "unconnected-(MDBT1-P1.10-Pad3)") (class "Default")
      (node (ref "MDBT1") (pin "3") (pinfunction "P1.10_3") (pintype "bidirectional"))
    )
    (net (code "67") (name "unconnected-(MDBT1-P1.11-Pad4)") (class "Default")
      (node (ref "MDBT1") (pin "4") (pinfunction "P1.11_4") (pintype "bidirectional"))
    )
    (net (code "68") (name "unconnected-(MDBT1-P1.12-Pad5)") (class "Default")
      (node (ref "MDBT1") (pin "5") (pinfunction "P1.12_5") (pintype "bidirectional"))
    )
    (net (code "69") (name "unconnected-(MDBT1-P1.13-Pad6)") (class "Default")
      (node (ref "MDBT1") (pin "6") (pinfunction "P1.13_6") (pintype "bidirectional"))
    )
    (net (code "70") (name "unconnected-(MDBT1-P1.14-Pad7)") (class "Default")
      (node (ref "MDBT1") (pin "7") (pinfunction "P1.14_7") (pintype "bidirectional"))
    )
    (net (code "71") (name "unconnected-(MDBT1-P1.15-Pad8)") (class "Default")
      (node (ref "MDBT1") (pin "8") (pinfunction "P1.15_8") (pintype "bidirectional"))
    )
    (net (code "72") (name "unconnected-(MDBT1-VBUS-Pad32)") (class "Default")
      (node (ref "MDBT1") (pin "32") (pinfunction "VBUS_32") (pintype "bidirectional"))
    )
    (net (code "73") (name "unconnected-(U1-ALERT{slash}RDY-Pad2)") (class "Default")
      (node (ref "U1") (pin "2") (pinfunction "ALERT/RDY_2") (pintype "input"))
    )
    (net (code "74") (name "unconnected-(U2-DEN_A{slash}G-Pad13)") (class "Default")
      (node (ref "U2") (pin "13") (pinfunction "DEN_A/G_13") (pintype "bidirectional"))
    )
    (net (code "75") (name "unconnected-(U2-DRDY_M-Pad9)") (class "Default")
      (node (ref "U2") (pin "9") (pinfunction "DRDY_M_9") (pintype "bidirectional"))
    )
    (net (code "76") (name "unconnected-(U2-INT1_A{slash}G-Pad11)") (class "Default")
      (node (ref "U2") (pin "11") (pinfunction "INT1_A/G_11") (pintype "bidirectional"))
    )
    (net (code "77") (name "unconnected-(U2-INT2_A{slash}G-Pad12)") (class "Default")
      (node (ref "U2") (pin "12") (pinfunction "INT2_A/G_12") (pintype "bidirectional"))
    )
    (net (code "78") (name "unconnected-(U2-INT_M-Pad10)") (class "Default")
      (node (ref "U2") (pin "10") (pinfunction "INT_M_10") (pintype "bidirectional"))
    )
    (net (code "79") (name "unconnected-(U4-NC-PadP$8)") (class "Default")
      (node (ref "U4") (pin "P$8") (pinfunction "NC_P$8") (pintype "bidirectional"))
    )
  )
)
